# Power.net
KiCad netlist of a schematic drawn in Altium Designer
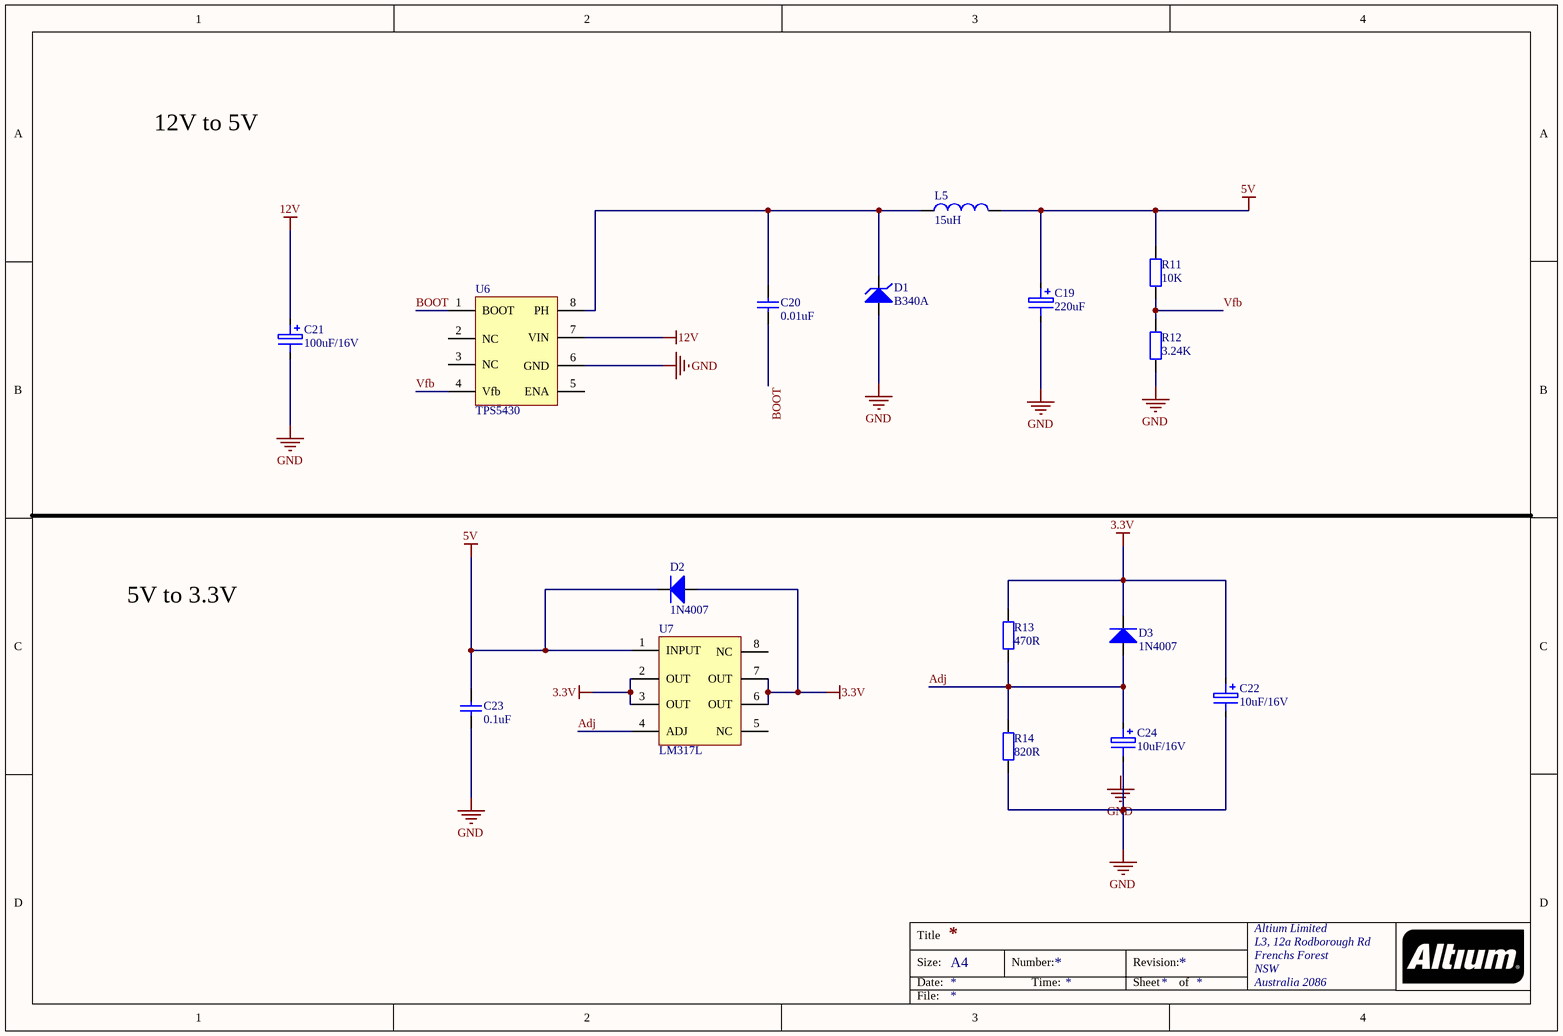
[diagram p0: Power.SchDoc]

(export (version "E")
  (design (tool "Eeschema 10.0.6"))
  (components
    (comp (ref "C19")
      (value "220uF")
      (footprint "CAPM-7.0*4.5")
      (description "aluminum")
      (libsource (lib "ToponLib") (part "Cap3"))
    )
    (comp (ref "C20")
      (value "0.01uF")
      (footprint "0603")
      (description "ceramic")
      (libsource (lib "ToponLib") (part "Cap1"))
    )
    (comp (ref "C21")
      (value "100uF/16V")
      (footprint "CAPM-7.0*4.5")
      (description "aluminum")
      (libsource (lib "ToponLib") (part "Cap3"))
    )
    (comp (ref "C22")
      (value "10uF/16V")
      (footprint "CAPM-5.5*3.3")
      (description "aluminum")
      (libsource (lib "ToponLib") (part "Cap3"))
    )
    (comp (ref "C23")
      (value "0.1uF")
      (footprint "0603")
      (description "ceramic")
      (libsource (lib "ToponLib") (part "Cap1"))
    )
    (comp (ref "C24")
      (value "10uF/16V")
      (footprint "CAPM-5.5*3.3")
      (description "aluminum")
      (libsource (lib "ToponLib") (part "Cap3"))
    )
    (comp (ref "D1") (value "B340A") (footprint "DO214-AC") (libsource (lib "ToponLib") (part "B340A-13-F")))
    (comp (ref "D2") (value "1N4007") (footprint "DO214-AC") (libsource (lib "ToponLib") (part "1N4007")))
    (comp (ref "D3") (value "1N4007") (footprint "DO214-AC") (libsource (lib "ToponLib") (part "1N4007")))
    (comp (ref "L5") (value "15uH") (footprint "7*7*4-15uH") (libsource (lib "ToponLib") (part "Inductor")))
    (comp (ref "R11") (value "10K") (footprint "0603") (libsource (lib "ToponLib") (part "Res")))
    (comp (ref "R12") (value "3.24K") (footprint "0603") (libsource (lib "ToponLib") (part "Res")))
    (comp (ref "R13") (value "470R") (footprint "0603") (libsource (lib "ToponLib") (part "Res")))
    (comp (ref "R14") (value "820R") (footprint "0603") (libsource (lib "ToponLib") (part "Res")))
    (comp (ref "U6") (value "TPS5430") (footprint "TPS5430") (libsource (lib "ToponLib") (part "TPS5430")))
    (comp (ref "U7") (value "LM317L") (footprint "LM317L") (libsource (lib "ToponLib") (part "LM317L")))
  )
  (nets
    (net (code "1") (name "/Adj") (class "Default")
      (node (ref "C24") (pin "1") (pinfunction "1_1") (pintype "passive"))
      (node (ref "D3") (pin "1") (pinfunction "A_1") (pintype "passive"))
      (node (ref "R13") (pin "1") (pinfunction "1_1") (pintype "passive"))
      (node (ref "R14") (pin "2") (pinfunction "2_2") (pintype "passive"))
      (node (ref "U7") (pin "4") (pinfunction "ADJ_4") (pintype "passive"))
    )
    (net (code "2") (name "/BOOT") (class "Default")
      (node (ref "C20") (pin "1") (pinfunction "1_1") (pintype "passive"))
      (node (ref "U6") (pin "1") (pinfunction "BOOT_1") (pintype "passive"))
    )
    (net (code "3") (name "/Vfb") (class "Default")
      (node (ref "R11") (pin "1") (pinfunction "1_1") (pintype "passive"))
      (node (ref "R12") (pin "2") (pinfunction "2_2") (pintype "passive"))
      (node (ref "U6") (pin "4") (pinfunction "Vfb_4") (pintype "passive"))
    )
    (net (code "4") (name "3.3V") (class "Default")
      (node (ref "C22") (pin "1") (pinfunction "1_1") (pintype "passive"))
      (node (ref "D2") (pin "1") (pinfunction "A_1") (pintype "passive"))
      (node (ref "D3") (pin "2") (pinfunction "K_2") (pintype "passive"))
      (node (ref "R13") (pin "2") (pinfunction "2_2") (pintype "passive"))
      (node (ref "U7") (pin "2") (pinfunction "OUT_2") (pintype "passive"))
      (node (ref "U7") (pin "3") (pinfunction "OUT_3") (pintype "passive"))
      (node (ref "U7") (pin "6") (pinfunction "OUT_6") (pintype "passive"))
      (node (ref "U7") (pin "7") (pinfunction "OUT_7") (pintype "passive"))
    )
    (net (code "5") (name "5V") (class "Default")
      (node (ref "C19") (pin "1") (pinfunction "1_1") (pintype "passive"))
      (node (ref "C23") (pin "2") (pinfunction "2_2") (pintype "passive"))
      (node (ref "D2") (pin "2") (pinfunction "K_2") (pintype "passive"))
      (node (ref "L5") (pin "2") (pinfunction "2_2") (pintype "passive"))
      (node (ref "R11") (pin "2") (pinfunction "2_2") (pintype "passive"))
      (node (ref "U7") (pin "1") (pinfunction "INPUT_1") (pintype "passive"))
    )
    (net (code "6") (name "12V") (class "Default")
      (node (ref "C21") (pin "1") (pinfunction "1_1") (pintype "passive"))
      (node (ref "U6") (pin "7") (pinfunction "VIN_7") (pintype "passive"))
    )
    (net (code "7") (name "GND") (class "Default")
      (node (ref "C19") (pin "2") (pinfunction "2_2") (pintype "passive"))
      (node (ref "C21") (pin "2") (pinfunction "2_2") (pintype "passive"))
      (node (ref "C22") (pin "2") (pinfunction "2_2") (pintype "passive"))
      (node (ref "C23") (pin "1") (pinfunction "1_1") (pintype "passive"))
      (node (ref "C24") (pin "2") (pinfunction "2_2") (pintype "passive"))
      (node (ref "D1") (pin "1") (pinfunction "A_1") (pintype "passive"))
      (node (ref "R12") (pin "1") (pinfunction "1_1") (pintype "passive"))
      (node (ref "R14") (pin "1") (pinfunction "1_1") (pintype "passive"))
      (node (ref "U6") (pin "6") (pinfunction "GND_6") (pintype "passive"))
    )
    (net (code "8") (name "Net-(D1-K)") (class "Default")
      (node (ref "C20") (pin "2") (pinfunction "2_2") (pintype "passive"))
      (node (ref "D1") (pin "2") (pinfunction "K_2") (pintype "passive"))
      (node (ref "L5") (pin "1") (pinfunction "1_1") (pintype "passive"))
      (node (ref "U6") (pin "8") (pinfunction "PH_8") (pintype "passive"))
    )
    (net (code "9") (name "unconnected-(U6-ENA-Pad5)") (class "Default")
      (node (ref "U6") (pin "5") (pinfunction "ENA_5") (pintype "passive"))
    )
    (net (code "10") (name "unconnected-(U6-NC-Pad2)") (class "Default")
      (node (ref "U6") (pin "2") (pinfunction "NC_2") (pintype "passive"))
    )
    (net (code "11") (name "unconnected-(U6-NC-Pad3)") (class "Default")
      (node (ref "U6") (pin "3") (pinfunction "NC_3") (pintype "passive"))
    )
    (net (code "12") (name "unconnected-(U7-NC-Pad5)") (class "Default")
      (node (ref "U7") (pin "5") (pinfunction "NC_5") (pintype "passive"))
    )
    (net (code "13") (name "unconnected-(U7-NC-Pad8)") (class "Default")
      (node (ref "U7") (pin "8") (pinfunction "NC_8") (pintype "passive"))
    )
  )
)
